# PowerCircuit.net
KiCad netlist of a schematic drawn in EAGLE
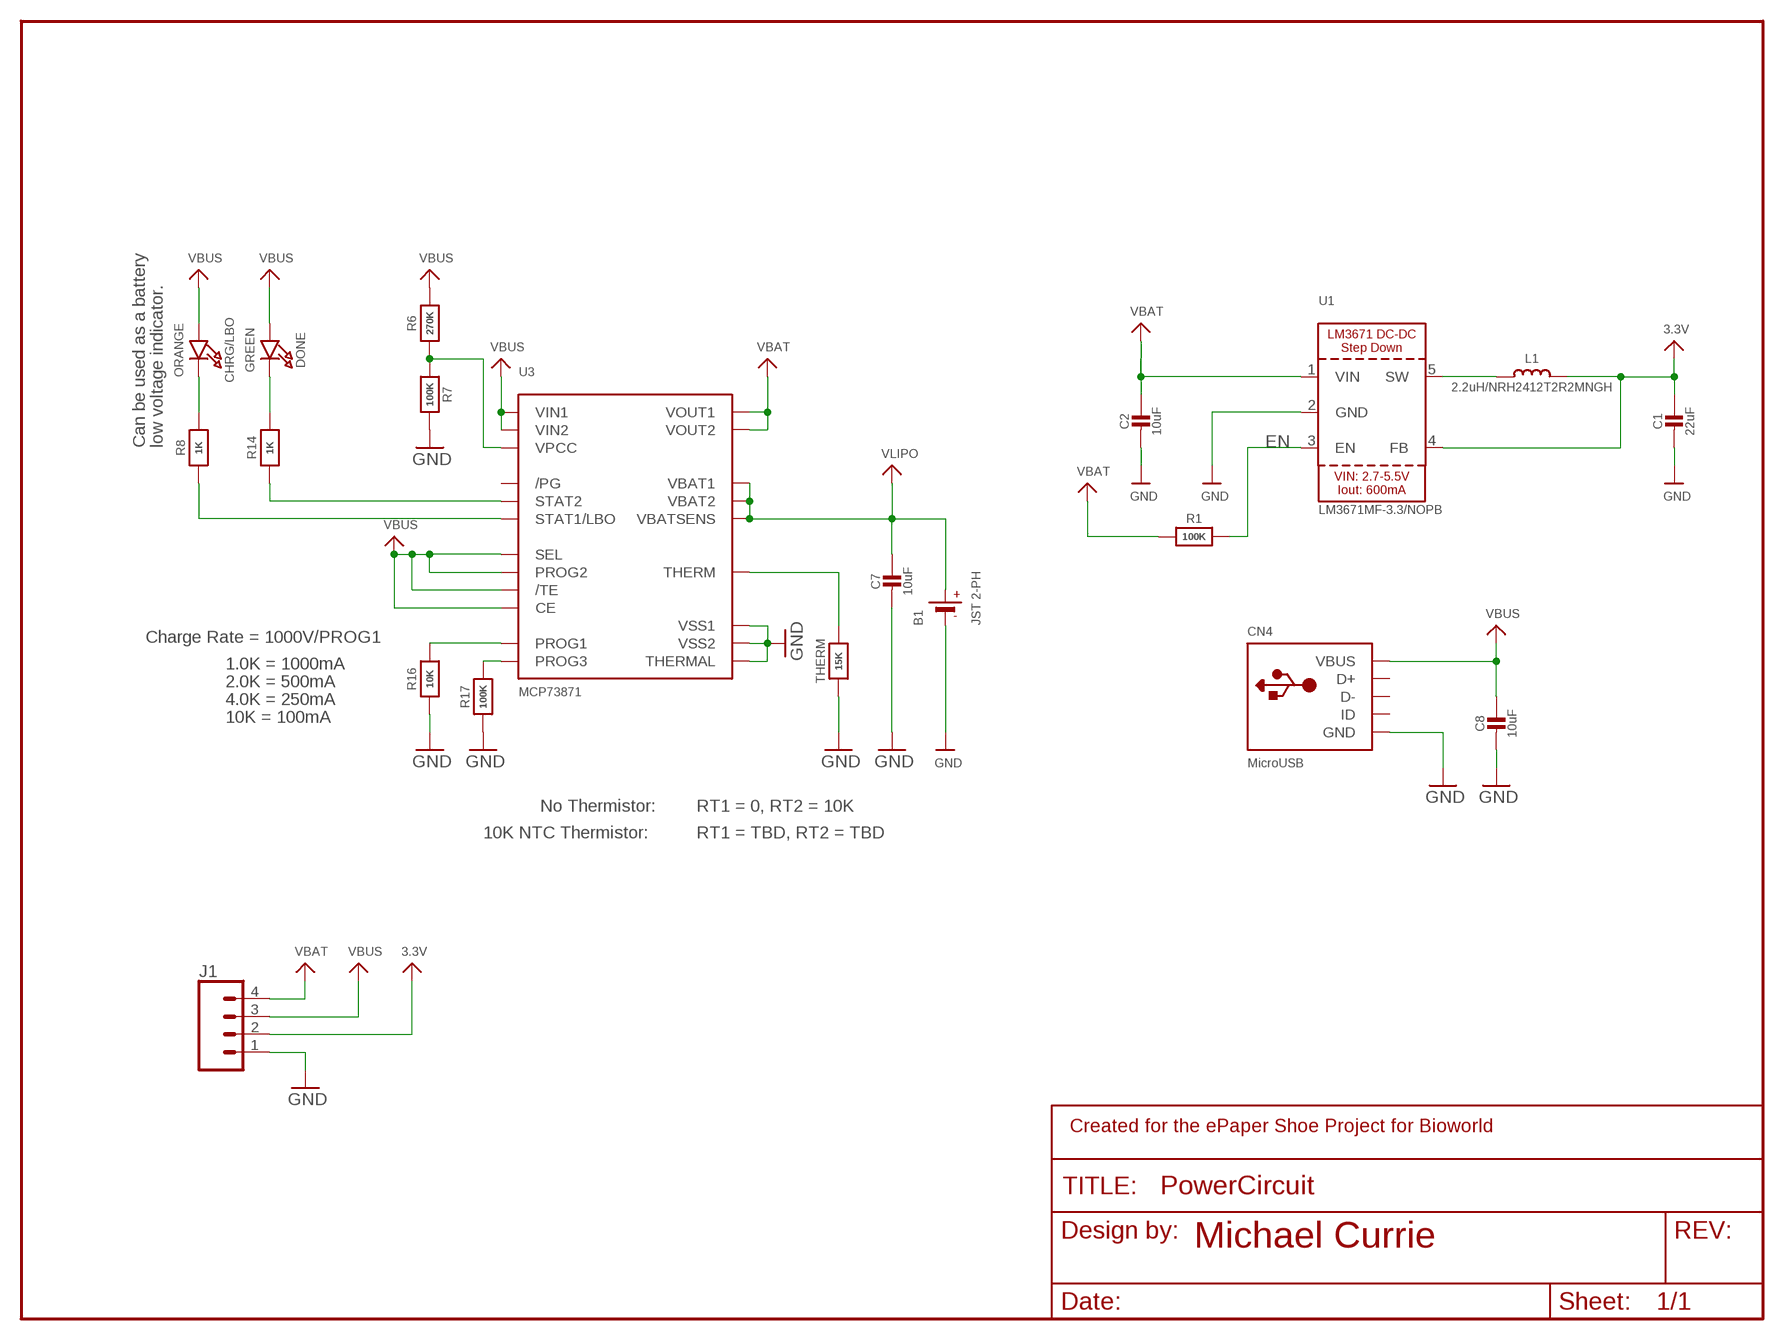
[diagram p0: schematic, sheet 1]

(export (version "E")
  (design (tool "Eeschema 10.0.6"))
  (components
    (comp (ref "B1")
      (value "JST 2-PH")
      (footprint "eagle-import:JSTPH2")
      (libsource (lib "eagle-import") (part "BATTERY"))
    )
    (comp (ref "C1")
      (value "22uF")
      (footprint "eagle-import:0805-NO")
      (libsource (lib "eagle-import") (part "CAP_CERAMIC0805-NOOUTLINE"))
    )
    (comp (ref "C2")
      (value "10uF")
      (footprint "eagle-import:0805-NO")
      (libsource (lib "eagle-import") (part "CAP_CERAMIC0805-NOOUTLINE"))
    )
    (comp (ref "C7")
      (value "10uF")
      (footprint "eagle-import:0805-NO")
      (libsource (lib "eagle-import") (part "CAP_CERAMIC0805-NOOUTLINE"))
    )
    (comp (ref "C8")
      (value "10uF")
      (footprint "eagle-import:0805-NO")
      (libsource (lib "eagle-import") (part "CAP_CERAMIC0805-NOOUTLINE"))
    )
    (comp (ref "CHRG/LBO")
      (value "ORANGE")
      (footprint "eagle-import:CHIPLED_0805_NOOUTLINE")
      (libsource (lib "eagle-import") (part "LED0805_NOOUTLINE"))
    )
    (comp (ref "CN4")
      (value "MicroUSB")
      (footprint "eagle-import:4UCONN_20329")
      (libsource (lib "eagle-import") (part "USBMICRO_20329"))
    )
    (comp (ref "DONE")
      (value "GREEN")
      (footprint "eagle-import:CHIPLED_0805_NOOUTLINE")
      (libsource (lib "eagle-import") (part "LED0805_NOOUTLINE"))
    )
    (comp (ref "FRAME1")
      (value "FRAME-LETTER-MICHAELNO_PACKAGE")
      (footprint "eagle-import:DUMMY")
      (fields (field (name "DESIGNER") "Nobody"))
      (libsource (lib "eagle-import") (part "FRAME-LETTER-MICHAELNO_PACKAGE"))
    )
    (comp (ref "J1")
      (value "CONN_04")
      (footprint "eagle-import:1X04")
      (libsource (lib "eagle-import") (part "CONN_04"))
    )
    (comp (ref "L1")
      (value "2.2uH/NRH2412T2R2MNGH")
      (footprint "eagle-import:INDUCTOR_TAIYOYUDEN_NRH2412T")
      (libsource (lib "eagle-import") (part "INDUCTORNRH2412T"))
    )
    (comp (ref "R1")
      (value "100K")
      (footprint "eagle-import:0805-NO")
      (libsource (lib "eagle-import") (part "RESISTOR0805_NOOUTLINE"))
    )
    (comp (ref "R6")
      (value "270K")
      (footprint "eagle-import:0805-NO")
      (libsource (lib "eagle-import") (part "RESISTOR0805_NOOUTLINE"))
    )
    (comp (ref "R7")
      (value "100K")
      (footprint "eagle-import:0805-NO")
      (libsource (lib "eagle-import") (part "RESISTOR0805_NOOUTLINE"))
    )
    (comp (ref "R8")
      (value "1K")
      (footprint "eagle-import:0805-NO")
      (libsource (lib "eagle-import") (part "RESISTOR0805_NOOUTLINE"))
    )
    (comp (ref "R14")
      (value "1K")
      (footprint "eagle-import:0805-NO")
      (libsource (lib "eagle-import") (part "RESISTOR0805_NOOUTLINE"))
    )
    (comp (ref "R16")
      (value "10K")
      (footprint "eagle-import:0805-NO")
      (libsource (lib "eagle-import") (part "RESISTOR0805_NOOUTLINE"))
    )
    (comp (ref "R17")
      (value "100K")
      (footprint "eagle-import:0805-NO")
      (libsource (lib "eagle-import") (part "RESISTOR0805_NOOUTLINE"))
    )
    (comp (ref "THERM")
      (value "15K")
      (footprint "eagle-import:0805-NO")
      (libsource (lib "eagle-import") (part "RESISTOR0805_NOOUTLINE"))
    )
    (comp (ref "U1")
      (value "LM3671MF-3.3/NOPB")
      (footprint "eagle-import:SOT23-5")
      (libsource (lib "eagle-import") (part "VREG_LM3671"))
    )
    (comp (ref "U3")
      (value "MCP73871")
      (footprint "eagle-import:QFN20_4MM")
      (libsource (lib "eagle-import") (part "MCP73871"))
    )
  )
  (nets
    (net (code "1") (name "/EN") (class "Default")
      (node (ref "R1") (pin "2") (pinfunction "2_2") (pintype "passive"))
      (node (ref "U1") (pin "3") (pinfunction "EN_3") (pintype "input"))
    )
    (net (code "2") (name "3.3V") (class "Default")
      (node (ref "C1") (pin "1") (pinfunction "1_1") (pintype "passive"))
      (node (ref "J1") (pin "2") (pinfunction "2_2") (pintype "passive"))
      (node (ref "L1") (pin "2") (pinfunction "2_2") (pintype "passive"))
      (node (ref "U1") (pin "4") (pinfunction "FB_4") (pintype "power_in"))
    )
    (net (code "3") (name "GND") (class "Default")
      (node (ref "B1") (pin "1") (pinfunction "-_1") (pintype "passive"))
      (node (ref "C1") (pin "2") (pinfunction "2_2") (pintype "passive"))
      (node (ref "C2") (pin "2") (pinfunction "2_2") (pintype "passive"))
      (node (ref "C7") (pin "2") (pinfunction "2_2") (pintype "passive"))
      (node (ref "C8") (pin "2") (pinfunction "2_2") (pintype "passive"))
      (node (ref "CN4") (pin "BASE@1") (pinfunction "GND_BASE@1") (pintype "power_in"))
      (node (ref "CN4") (pin "BASE@2") (pinfunction "GND_BASE@2") (pintype "power_in"))
      (node (ref "CN4") (pin "GND") (pinfunction "GND_GND") (pintype "power_in"))
      (node (ref "CN4") (pin "SPRT@1") (pinfunction "GND_SPRT@1") (pintype "power_in"))
      (node (ref "CN4") (pin "SPRT@2") (pinfunction "GND_SPRT@2") (pintype "power_in"))
      (node (ref "CN4") (pin "SPRT@3") (pinfunction "GND_SPRT@3") (pintype "power_in"))
      (node (ref "CN4") (pin "SPRT@4") (pinfunction "GND_SPRT@4") (pintype "power_in"))
      (node (ref "J1") (pin "1") (pinfunction "1_1") (pintype "passive"))
      (node (ref "R16") (pin "1") (pinfunction "1_1") (pintype "passive"))
      (node (ref "R17") (pin "1") (pinfunction "1_1") (pintype "passive"))
      (node (ref "R7") (pin "2") (pinfunction "2_2") (pintype "passive"))
      (node (ref "THERM") (pin "1") (pinfunction "1_1") (pintype "passive"))
      (node (ref "U1") (pin "2") (pinfunction "GND_2") (pintype "power_in"))
      (node (ref "U3") (pin "P$10") (pinfunction "VSS1_P$10") (pintype "bidirectional"))
      (node (ref "U3") (pin "P$11") (pinfunction "VSS2_P$11") (pintype "bidirectional"))
      (node (ref "U3") (pin "P$21") (pinfunction "THERMAL_P$21") (pintype "bidirectional"))
    )
    (net (code "4") (name "Net-(CHRG/LBO-PadC)") (class "Default")
      (node (ref "CHRG/LBO") (pin "C") (pinfunction "C_C") (pintype "passive"))
      (node (ref "R8") (pin "2") (pinfunction "2_2") (pintype "passive"))
    )
    (net (code "5") (name "Net-(DONE-PadC)") (class "Default")
      (node (ref "DONE") (pin "C") (pinfunction "C_C") (pintype "passive"))
      (node (ref "R14") (pin "2") (pinfunction "2_2") (pintype "passive"))
    )
    (net (code "6") (name "Net-(U1-SW)") (class "Default")
      (node (ref "L1") (pin "1") (pinfunction "1_1") (pintype "passive"))
      (node (ref "U1") (pin "5") (pinfunction "SW_5") (pintype "output"))
    )
    (net (code "7") (name "Net-(U3-PROG1)") (class "Default")
      (node (ref "R16") (pin "2") (pinfunction "2_2") (pintype "passive"))
      (node (ref "U3") (pin "P$13") (pinfunction "PROG1_P$13") (pintype "bidirectional"))
    )
    (net (code "8") (name "Net-(U3-PROG3)") (class "Default")
      (node (ref "R17") (pin "2") (pinfunction "2_2") (pintype "passive"))
      (node (ref "U3") (pin "P$12") (pinfunction "PROG3_P$12") (pintype "bidirectional"))
    )
    (net (code "9") (name "Net-(U3-STAT1{slash}LBO)") (class "Default")
      (node (ref "R8") (pin "1") (pinfunction "1_1") (pintype "passive"))
      (node (ref "U3") (pin "P$8") (pinfunction "STAT1/LBO_P$8") (pintype "bidirectional"))
    )
    (net (code "10") (name "Net-(U3-STAT2)") (class "Default")
      (node (ref "R14") (pin "1") (pinfunction "1_1") (pintype "passive"))
      (node (ref "U3") (pin "P$7") (pinfunction "STAT2_P$7") (pintype "bidirectional"))
    )
    (net (code "11") (name "Net-(U3-THERM)") (class "Default")
      (node (ref "THERM") (pin "2") (pinfunction "2_2") (pintype "passive"))
      (node (ref "U3") (pin "P$5") (pinfunction "THERM_P$5") (pintype "bidirectional"))
    )
    (net (code "12") (name "Net-(U3-VPCC)") (class "Default")
      (node (ref "R6") (pin "1") (pinfunction "1_1") (pintype "passive"))
      (node (ref "R7") (pin "1") (pinfunction "1_1") (pintype "passive"))
      (node (ref "U3") (pin "P$2") (pinfunction "VPCC_P$2") (pintype "bidirectional"))
    )
    (net (code "13") (name "VBAT") (class "Default")
      (node (ref "C2") (pin "1") (pinfunction "1_1") (pintype "passive"))
      (node (ref "J1") (pin "4") (pinfunction "4_4") (pintype "passive"))
      (node (ref "R1") (pin "1") (pinfunction "1_1") (pintype "passive"))
      (node (ref "U1") (pin "1") (pinfunction "VIN_1") (pintype "power_in"))
      (node (ref "U3") (pin "P$1") (pinfunction "VOUT1_P$1") (pintype "bidirectional"))
      (node (ref "U3") (pin "P$20") (pinfunction "VOUT2_P$20") (pintype "bidirectional"))
    )
    (net (code "14") (name "VBUS") (class "Default")
      (node (ref "C8") (pin "1") (pinfunction "1_1") (pintype "passive"))
      (node (ref "CHRG/LBO") (pin "A") (pinfunction "A_A") (pintype "passive"))
      (node (ref "CN4") (pin "VBUS") (pinfunction "VBUS_VBUS") (pintype "power_in"))
      (node (ref "DONE") (pin "A") (pinfunction "A_A") (pintype "passive"))
      (node (ref "J1") (pin "3") (pinfunction "3_3") (pintype "passive"))
      (node (ref "R6") (pin "2") (pinfunction "2_2") (pintype "passive"))
      (node (ref "U3") (pin "P$17") (pinfunction "CE_P$17") (pintype "bidirectional"))
      (node (ref "U3") (pin "P$18") (pinfunction "VIN1_P$18") (pintype "bidirectional"))
      (node (ref "U3") (pin "P$19") (pinfunction "VIN2_P$19") (pintype "bidirectional"))
      (node (ref "U3") (pin "P$3") (pinfunction "SEL_P$3") (pintype "bidirectional"))
      (node (ref "U3") (pin "P$4") (pinfunction "PROG2_P$4") (pintype "bidirectional"))
      (node (ref "U3") (pin "P$9") (pinfunction "/TE_P$9") (pintype "bidirectional"))
    )
    (net (code "15") (name "VLIPO") (class "Default")
      (node (ref "B1") (pin "2") (pinfunction "+_2") (pintype "passive"))
      (node (ref "C7") (pin "1") (pinfunction "1_1") (pintype "passive"))
      (node (ref "U3") (pin "P$14") (pinfunction "VBAT1_P$14") (pintype "bidirectional"))
      (node (ref "U3") (pin "P$15") (pinfunction "VBAT2_P$15") (pintype "bidirectional"))
      (node (ref "U3") (pin "P$16") (pinfunction "VBATSENS_P$16") (pintype "bidirectional"))
    )
    (net (code "16") (name "unconnected-(CN4-PadD+)") (class "Default")
      (node (ref "CN4") (pin "D+") (pinfunction "D+_D+") (pintype "bidirectional"))
    )
    (net (code "17") (name "unconnected-(CN4-PadD-)") (class "Default")
      (node (ref "CN4") (pin "D-") (pinfunction "D-_D-") (pintype "bidirectional"))
    )
    (net (code "18") (name "unconnected-(CN4-PadID)") (class "Default")
      (node (ref "CN4") (pin "ID") (pinfunction "ID_ID") (pintype "bidirectional"))
    )
    (net (code "19") (name "unconnected-(U3-{slash}PG-PadP$6)") (class "Default")
      (node (ref "U3") (pin "P$6") (pinfunction "/PG_P$6") (pintype "bidirectional"))
    )
  )
)
